# Silent_Stepper_Driver_X_Axis.net
KiCad netlist of a schematic drawn in EAGLE
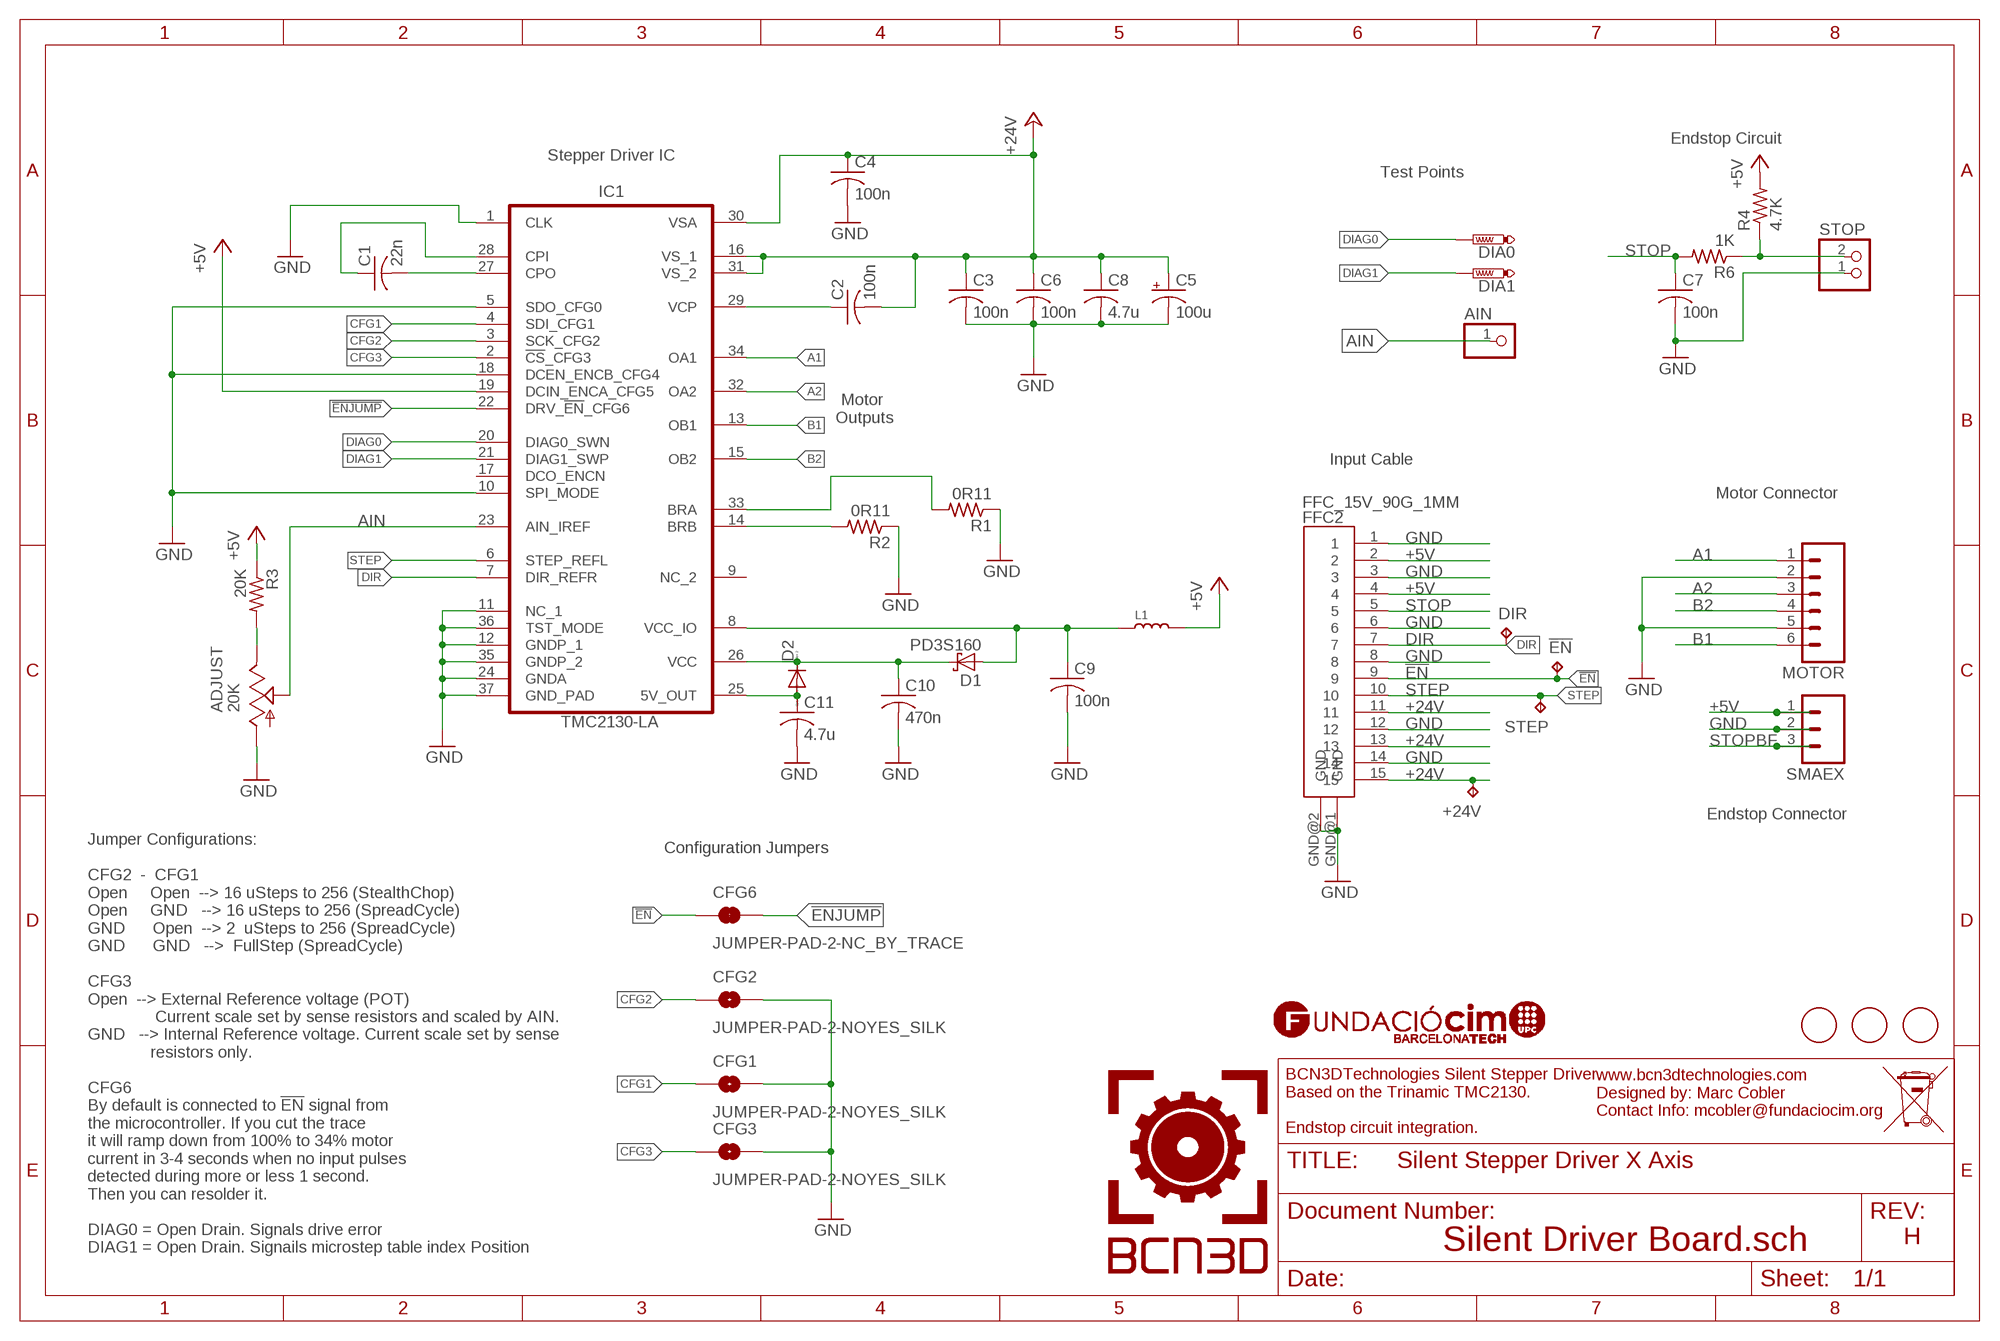
[diagram p0: schematic, sheet 1]

(export (version "E")
  (design (tool "Eeschema 10.0.6"))
  (components
    (comp (ref "!EN")
      (value "TPB1,27")
      (footprint "eagle-import:B1,27")
      (libsource (lib "eagle-import") (part "TPB1,27"))
    )
    (comp (ref "+24V")
      (value "TPB1,27")
      (footprint "eagle-import:B1,27")
      (libsource (lib "eagle-import") (part "TPB1,27"))
    )
    (comp (ref "ADJUST")
      (value "20K")
      (footprint "eagle-import:3223G")
      (fields (field (name "MF") "BOURNS") (field (name "MPN") "3314G-2-203E"))
      (libsource (lib "eagle-import") (part "TRIM_US-3223G"))
    )
    (comp (ref "AIN")
      (value "PINHD-1X1")
      (footprint "eagle-import:1X01")
      (libsource (lib "eagle-import") (part "PINHD-1X1"))
    )
    (comp (ref "C1")
      (value "22n")
      (footprint "eagle-import:C0603K")
      (fields (field (name "MF") "MURATA") (field (name "MPN") "GCM188R72A223KA37D"))
      (libsource (lib "eagle-import") (part "C-USC0603K"))
    )
    (comp (ref "C2")
      (value "100n")
      (footprint "eagle-import:C0603K")
      (fields (field (name "MF") "AVX") (field (name "MPN") "06035C104KAT2A"))
      (libsource (lib "eagle-import") (part "C-USC0603K"))
    )
    (comp (ref "C3")
      (value "100n")
      (footprint "eagle-import:C0603K")
      (fields (field (name "MF") "AVX") (field (name "MPN") "06035C104KAT2A"))
      (libsource (lib "eagle-import") (part "C-USC0603K"))
    )
    (comp (ref "C4")
      (value "100n")
      (footprint "eagle-import:C0603K")
      (fields (field (name "MF") "AVX") (field (name "MPN") "06035C104KAT2A"))
      (libsource (lib "eagle-import") (part "C-USC0603K"))
    )
    (comp (ref "C5")
      (value "100u")
      (footprint "eagle-import:UD-6,3X7,7_NICHICON")
      (fields (field (name "MF") "PANASONIC ELECTRONIC COMPONENTS") (field (name "MPN") "EEE1HA101UAP"))
      (libsource (lib "eagle-import") (part "CPOL-USUD-6,3X7,7"))
    )
    (comp (ref "C6")
      (value "100n")
      (footprint "eagle-import:C0603K")
      (fields (field (name "MF") "AVX") (field (name "MPN") "06035C104KAT2A"))
      (libsource (lib "eagle-import") (part "C-USC0603K"))
    )
    (comp (ref "C7")
      (value "100n")
      (footprint "eagle-import:C0603K")
      (fields (field (name "MF") "AVX") (field (name "MPN") "06035C104KAT2A"))
      (libsource (lib "eagle-import") (part "C-USC0603K"))
    )
    (comp (ref "C8")
      (value "4.7u")
      (footprint "eagle-import:C1210")
      (fields (field (name "MF") "KEMET") (field (name "MPN") "C1210X475K5RACTU"))
      (libsource (lib "eagle-import") (part "C-USC1210"))
    )
    (comp (ref "C9")
      (value "100n")
      (footprint "eagle-import:C0603K")
      (fields (field (name "MF") "AVX") (field (name "MPN") "06035C104KAT2A"))
      (libsource (lib "eagle-import") (part "C-USC0603K"))
    )
    (comp (ref "C10")
      (value "470n")
      (footprint "eagle-import:C0603K")
      (fields (field (name "MF") "MURATA") (field (name "MPN") "GRM188R71C474KA88D"))
      (libsource (lib "eagle-import") (part "C-USC0603K"))
    )
    (comp (ref "C11")
      (value "4.7u")
      (footprint "eagle-import:C0805")
      (fields (field (name "MF") "AVX") (field (name "MPN") "0805YC475KAT2A"))
      (libsource (lib "eagle-import") (part "C-USC0805"))
    )
    (comp (ref "CFG1")
      (value "JUMPER-PAD-2-NOYES_SILK")
      (footprint "eagle-import:PAD-JUMPER-2-NO_YES_SILK")
      (libsource (lib "eagle-import") (part "JUMPER-PAD-2-NOYES_SILK"))
    )
    (comp (ref "CFG2")
      (value "JUMPER-PAD-2-NOYES_SILK")
      (footprint "eagle-import:PAD-JUMPER-2-NO_YES_SILK")
      (libsource (lib "eagle-import") (part "JUMPER-PAD-2-NOYES_SILK"))
    )
    (comp (ref "CFG3")
      (value "JUMPER-PAD-2-NOYES_SILK")
      (footprint "eagle-import:PAD-JUMPER-2-NO_YES_SILK")
      (libsource (lib "eagle-import") (part "JUMPER-PAD-2-NOYES_SILK"))
    )
    (comp (ref "CFG6")
      (value "JUMPER-PAD-2-NC_BY_TRACE")
      (footprint "eagle-import:PAD-JUMPER-2-NC_BY_TRACE_YES_SILK")
      (libsource (lib "eagle-import") (part "JUMPER-PAD-2-NC_BY_TRACE"))
    )
    (comp (ref "D1")
      (value "PD3S160")
      (footprint "eagle-import:POWERDI323")
      (fields (field (name "MF") "DIODES INC.") (field (name "MPN") "PD3S160-7"))
      (libsource (lib "eagle-import") (part "PD3S160"))
    )
    (comp (ref "D2")
      (value "DIODE-MINIMELF")
      (footprint "eagle-import:MINIMELF")
      (fields (field (name "MF") "NXP") (field (name "MPN") "PMLL4448"))
      (libsource (lib "eagle-import") (part "DIODE-MINIMELF"))
    )
    (comp (ref "DIA0")
      (value "PTR1TP12R")
      (footprint "eagle-import:TP12R")
      (libsource (lib "eagle-import") (part "PTR1TP12R"))
    )
    (comp (ref "DIA1")
      (value "PTR1TP12R")
      (footprint "eagle-import:TP12R")
      (libsource (lib "eagle-import") (part "PTR1TP12R"))
    )
    (comp (ref "DIR")
      (value "TPB1,27")
      (footprint "eagle-import:B1,27")
      (libsource (lib "eagle-import") (part "TPB1,27"))
    )
    (comp (ref "FFC2")
      (value "FFC_15V_90G_1MM")
      (footprint "eagle-import:TE_FFC_CON1MM")
      (libsource (lib "eagle-import") (part "FFC_15V_90G_1MM"))
    )
    (comp (ref "IC1")
      (value "TMC2130-LA")
      (footprint "eagle-import:TMC_QFN36_0.5_5.0X6.0")
      (fields (field (name "MANUFACTURER") " TRINAMIC "))
      (libsource (lib "eagle-import") (part "TMC2130-LA"))
    )
    (comp (ref "L1")
      (value "INDUCTOR/FERRITE-BEAD'0603'")
      (footprint "eagle-import:L0603")
      (fields (field (name "MF") "BOURNS") (field (name "MPN") "CRL0603-FW-R470ELF"))
      (libsource (lib "eagle-import") (part "INDUCTOR/FERRITE-BEAD'0603'"))
    )
    (comp (ref "MOTOR")
      (value "M06")
      (footprint "eagle-import:JST-6-PTH")
      (fields
        (field (name "MF") "JST (JAPAN SOLDERLESS TERMINALS)")
        (field (name "MPN") "S6B-PH-K-S (LF)(SN)")
      )
      (libsource (lib "eagle-import") (part "M06"))
    )
    (comp (ref "R1")
      (value "0R11")
      (footprint "eagle-import:R0805")
      (fields (field (name "MF") "PANASONIC ELECTRONIC COMPONENTS") (field (name "MPN") "ERJ6BSFR11V"))
      (libsource (lib "eagle-import") (part "R-US_R0805"))
    )
    (comp (ref "R2")
      (value "0R11")
      (footprint "eagle-import:R0805")
      (fields (field (name "MF") "PANASONIC ELECTRONIC COMPONENTS") (field (name "MPN") "ERJ6BSFR11V"))
      (libsource (lib "eagle-import") (part "R-US_R0805"))
    )
    (comp (ref "R3")
      (value "20K")
      (footprint "eagle-import:R0603")
      (fields (field (name "MF") "MULTICOMP") (field (name "MPN") "MC0201L6F2002SE."))
      (libsource (lib "eagle-import") (part "R-US_R0603"))
    )
    (comp (ref "R4")
      (value "4.7K")
      (footprint "eagle-import:R0603")
      (fields (field (name "MF") "PANASONIC ELECTRONIC COMPONENTS") (field (name "MPN") "ERJP06F4701V"))
      (libsource (lib "eagle-import") (part "R-US_R0603"))
    )
    (comp (ref "R6")
      (value "1K")
      (footprint "eagle-import:R0603")
      (fields (field (name "MF") "BOURNS") (field (name "MPN") "CR0805-JW-102ELF"))
      (libsource (lib "eagle-import") (part "R-US_R0603"))
    )
    (comp (ref "SMAEX")
      (value "M03PTH")
      (footprint "eagle-import:1X03")
      (libsource (lib "eagle-import") (part "M03PTH"))
    )
    (comp (ref "STEP")
      (value "TPB1,27")
      (footprint "eagle-import:B1,27")
      (libsource (lib "eagle-import") (part "TPB1,27"))
    )
    (comp (ref "STOP")
      (value "JST_2PIN-THM-RA")
      (footprint "eagle-import:JST-PH-2-THM-RA")
      (fields
        (field (name "MF") "JST (JAPAN SOLDERLESS TERMINALS)")
        (field (name "MPN") "S2B-PH-K-S (LF)(SN)")
      )
      (libsource (lib "eagle-import") (part "JST_2PIN-THM-RA"))
    )
    (comp (ref "U$2")
      (value "FIDUCIAL")
      (footprint "eagle-import:FIDUCIAL_1MM")
      (libsource (lib "eagle-import") (part "FIDUCIAL"))
    )
    (comp (ref "U$3")
      (value "FIDUCIAL")
      (footprint "eagle-import:FIDUCIAL_1MM")
      (libsource (lib "eagle-import") (part "FIDUCIAL"))
    )
    (comp (ref "U$4")
      (value "FIDUCIAL")
      (footprint "eagle-import:FIDUCIAL_1MM")
      (libsource (lib "eagle-import") (part "FIDUCIAL"))
    )
  )
  (nets
    (net (code "1") (name "+5V") (class "Default")
      (node (ref "FFC2") (pin "2") (pinfunction "2_2") (pintype "bidirectional"))
      (node (ref "FFC2") (pin "4") (pinfunction "4_4") (pintype "bidirectional"))
      (node (ref "IC1") (pin "19") (pinfunction "DCIN_ENCA_CFG5_19") (pintype "input"))
      (node (ref "L1") (pin "2") (pinfunction "2_2") (pintype "passive"))
      (node (ref "R3") (pin "1") (pinfunction "1_1") (pintype "passive"))
      (node (ref "R4") (pin "2") (pinfunction "2_2") (pintype "passive"))
      (node (ref "SMAEX") (pin "1") (pinfunction "1_1") (pintype "passive"))
    )
    (net (code "2") (name "+24V") (class "Default")
      (node (ref "+24V") (pin "TP") (pinfunction "TP_TP") (pintype "input"))
      (node (ref "C2") (pin "2") (pinfunction "2_2") (pintype "passive"))
      (node (ref "C3") (pin "1") (pinfunction "1_1") (pintype "passive"))
      (node (ref "C4") (pin "1") (pinfunction "1_1") (pintype "passive"))
      (node (ref "C5") (pin "+") (pinfunction "+_+") (pintype "passive"))
      (node (ref "C6") (pin "1") (pinfunction "1_1") (pintype "passive"))
      (node (ref "C8") (pin "1") (pinfunction "1_1") (pintype "passive"))
      (node (ref "FFC2") (pin "11") (pinfunction "11_11") (pintype "bidirectional"))
      (node (ref "FFC2") (pin "13") (pinfunction "13_13") (pintype "bidirectional"))
      (node (ref "FFC2") (pin "15") (pinfunction "15_15") (pintype "bidirectional"))
      (node (ref "IC1") (pin "16") (pinfunction "VS_1_16") (pintype "power_in"))
      (node (ref "IC1") (pin "30") (pinfunction "VSA_30") (pintype "power_in"))
      (node (ref "IC1") (pin "31") (pinfunction "VS_2_31") (pintype "power_in"))
    )
    (net (code "3") (name "/STOP") (class "Default")
      (node (ref "C7") (pin "1") (pinfunction "1_1") (pintype "passive"))
      (node (ref "FFC2") (pin "5") (pinfunction "5_5") (pintype "bidirectional"))
      (node (ref "R6") (pin "2") (pinfunction "2_2") (pintype "passive"))
    )
    (net (code "4") (name "/STOPBF") (class "Default")
      (node (ref "R4") (pin "1") (pinfunction "1_1") (pintype "passive"))
      (node (ref "R6") (pin "1") (pinfunction "1_1") (pintype "passive"))
      (node (ref "SMAEX") (pin "3") (pinfunction "3_3") (pintype "passive"))
      (node (ref "STOP") (pin "2") (pinfunction "1_2") (pintype "passive"))
    )
    (net (code "5") (name "/~{ENJUMP}") (class "Default")
      (node (ref "CFG6") (pin "2") (pinfunction "2_2") (pintype "passive"))
      (node (ref "IC1") (pin "22") (pinfunction "DRV_~{EN}_CFG6_22") (pintype "input"))
    )
    (net (code "6") (name "/~{EN}") (class "Default")
      (node (ref "!EN") (pin "TP") (pinfunction "TP_TP") (pintype "input"))
      (node (ref "CFG6") (pin "1") (pinfunction "1_1") (pintype "passive"))
      (node (ref "FFC2") (pin "9") (pinfunction "9_9") (pintype "bidirectional"))
    )
    (net (code "7") (name "A1") (class "Default")
      (node (ref "IC1") (pin "34") (pinfunction "OA1_34") (pintype "output"))
      (node (ref "MOTOR") (pin "1") (pinfunction "1_1") (pintype "passive"))
    )
    (net (code "8") (name "A2") (class "Default")
      (node (ref "IC1") (pin "32") (pinfunction "OA2_32") (pintype "output"))
      (node (ref "MOTOR") (pin "3") (pinfunction "3_3") (pintype "passive"))
    )
    (net (code "9") (name "AIN") (class "Default")
      (node (ref "ADJUST") (pin "2") (pinfunction "S_2") (pintype "passive"))
      (node (ref "AIN") (pin "1") (pinfunction "1_1") (pintype "passive"))
      (node (ref "IC1") (pin "23") (pinfunction "AIN_IREF_23") (pintype "input"))
    )
    (net (code "10") (name "B1") (class "Default")
      (node (ref "IC1") (pin "13") (pinfunction "OB1_13") (pintype "output"))
      (node (ref "MOTOR") (pin "6") (pinfunction "6_6") (pintype "passive"))
    )
    (net (code "11") (name "B2") (class "Default")
      (node (ref "IC1") (pin "15") (pinfunction "OB2_15") (pintype "output"))
      (node (ref "MOTOR") (pin "4") (pinfunction "4_4") (pintype "passive"))
    )
    (net (code "12") (name "CFG1") (class "Default")
      (node (ref "CFG1") (pin "1") (pinfunction "1_1") (pintype "passive"))
      (node (ref "IC1") (pin "4") (pinfunction "SDI_CFG1_4") (pintype "input"))
    )
    (net (code "13") (name "CFG2") (class "Default")
      (node (ref "CFG2") (pin "1") (pinfunction "1_1") (pintype "passive"))
      (node (ref "IC1") (pin "3") (pinfunction "SCK_CFG2_3") (pintype "input"))
    )
    (net (code "14") (name "CFG3") (class "Default")
      (node (ref "CFG3") (pin "1") (pinfunction "1_1") (pintype "passive"))
      (node (ref "IC1") (pin "2") (pinfunction "~{CS}_CFG3_2") (pintype "input"))
    )
    (net (code "15") (name "DIAG0") (class "Default")
      (node (ref "DIA0") (pin "TP") (pinfunction "TP_TP") (pintype "input"))
      (node (ref "IC1") (pin "20") (pinfunction "DIAG0_SWN_20") (pintype "bidirectional"))
    )
    (net (code "16") (name "DIAG1") (class "Default")
      (node (ref "DIA1") (pin "TP") (pinfunction "TP_TP") (pintype "input"))
      (node (ref "IC1") (pin "21") (pinfunction "DIAG1_SWP_21") (pintype "bidirectional"))
    )
    (net (code "17") (name "DIR") (class "Default")
      (node (ref "DIR") (pin "TP") (pinfunction "TP_TP") (pintype "input"))
      (node (ref "FFC2") (pin "7") (pinfunction "7_7") (pintype "bidirectional"))
      (node (ref "IC1") (pin "7") (pinfunction "DIR_REFR_7") (pintype "input"))
    )
    (net (code "18") (name "GND") (class "Default")
      (node (ref "ADJUST") (pin "1") (pinfunction "A_1") (pintype "passive"))
      (node (ref "C10") (pin "2") (pinfunction "2_2") (pintype "passive"))
      (node (ref "C11") (pin "2") (pinfunction "2_2") (pintype "passive"))
      (node (ref "C3") (pin "2") (pinfunction "2_2") (pintype "passive"))
      (node (ref "C4") (pin "2") (pinfunction "2_2") (pintype "passive"))
      (node (ref "C5") (pin "-") (pinfunction "-_-") (pintype "passive"))
      (node (ref "C6") (pin "2") (pinfunction "2_2") (pintype "passive"))
      (node (ref "C7") (pin "2") (pinfunction "2_2") (pintype "passive"))
      (node (ref "C8") (pin "2") (pinfunction "2_2") (pintype "passive"))
      (node (ref "C9") (pin "2") (pinfunction "2_2") (pintype "passive"))
      (node (ref "CFG1") (pin "2") (pinfunction "2_2") (pintype "passive"))
      (node (ref "CFG2") (pin "2") (pinfunction "2_2") (pintype "passive"))
      (node (ref "CFG3") (pin "2") (pinfunction "2_2") (pintype "passive"))
      (node (ref "FFC2") (pin "1") (pinfunction "1_1") (pintype "bidirectional"))
      (node (ref "FFC2") (pin "12") (pinfunction "12_12") (pintype "bidirectional"))
      (node (ref "FFC2") (pin "14") (pinfunction "14_14") (pintype "bidirectional"))
      (node (ref "FFC2") (pin "3") (pinfunction "3_3") (pintype "bidirectional"))
      (node (ref "FFC2") (pin "6") (pinfunction "6_6") (pintype "bidirectional"))
      (node (ref "FFC2") (pin "8") (pinfunction "8_8") (pintype "bidirectional"))
      (node (ref "FFC2") (pin "GND@1") (pinfunction "GND_GND@1") (pintype "bidirectional"))
      (node (ref "FFC2") (pin "GND@2") (pinfunction "GND_GND@2") (pintype "bidirectional"))
      (node (ref "IC1") (pin "1") (pinfunction "CLK_1") (pintype "input"))
      (node (ref "IC1") (pin "10") (pinfunction "SPI_MODE_10") (pintype "input"))
      (node (ref "IC1") (pin "11") (pinfunction "NC_1_11") (pintype "power_in"))
      (node (ref "IC1") (pin "12") (pinfunction "GNDP_1_12") (pintype "power_in"))
      (node (ref "IC1") (pin "18") (pinfunction "DCEN_ENCB_CFG4_18") (pintype "input"))
      (node (ref "IC1") (pin "24") (pinfunction "GNDA_24") (pintype "power_in"))
      (node (ref "IC1") (pin "35") (pinfunction "GNDP_2_35") (pintype "power_in"))
      (node (ref "IC1") (pin "36") (pinfunction "TST_MODE_36") (pintype "input"))
      (node (ref "IC1") (pin "37") (pinfunction "GND_PAD_37") (pintype "power_in"))
      (node (ref "IC1") (pin "5") (pinfunction "SDO_CFG0_5") (pintype "bidirectional"))
      (node (ref "MOTOR") (pin "2") (pinfunction "2_2") (pintype "passive"))
      (node (ref "MOTOR") (pin "5") (pinfunction "5_5") (pintype "passive"))
      (node (ref "R1") (pin "1") (pinfunction "1_1") (pintype "passive"))
      (node (ref "R2") (pin "1") (pinfunction "1_1") (pintype "passive"))
      (node (ref "SMAEX") (pin "2") (pinfunction "2_2") (pintype "passive"))
      (node (ref "STOP") (pin "1") (pinfunction "2_1") (pintype "passive"))
    )
    (net (code "19") (name "Net-(ADJUST-E)") (class "Default")
      (node (ref "ADJUST") (pin "3") (pinfunction "E_3") (pintype "passive"))
      (node (ref "R3") (pin "2") (pinfunction "2_2") (pintype "passive"))
    )
    (net (code "20") (name "Net-(IC1-5V_OUT)") (class "Default")
      (node (ref "C11") (pin "1") (pinfunction "1_1") (pintype "passive"))
      (node (ref "D2") (pin "A") (pinfunction "A_A") (pintype "passive"))
      (node (ref "IC1") (pin "25") (pinfunction "5V_OUT_25") (pintype "power_in"))
    )
    (net (code "21") (name "Net-(IC1-BRA)") (class "Default")
      (node (ref "IC1") (pin "33") (pinfunction "BRA_33") (pintype "output"))
      (node (ref "R1") (pin "2") (pinfunction "2_2") (pintype "passive"))
    )
    (net (code "22") (name "Net-(IC1-BRB)") (class "Default")
      (node (ref "IC1") (pin "14") (pinfunction "BRB_14") (pintype "output"))
      (node (ref "R2") (pin "2") (pinfunction "2_2") (pintype "passive"))
    )
    (net (code "23") (name "Net-(IC1-CPI)") (class "Default")
      (node (ref "C1") (pin "1") (pinfunction "1_1") (pintype "passive"))
      (node (ref "IC1") (pin "28") (pinfunction "CPI_28") (pintype "input"))
    )
    (net (code "24") (name "Net-(IC1-CPO)") (class "Default")
      (node (ref "C1") (pin "2") (pinfunction "2_2") (pintype "passive"))
      (node (ref "IC1") (pin "27") (pinfunction "CPO_27") (pintype "output"))
    )
    (net (code "25") (name "Net-(IC1-VCC)") (class "Default")
      (node (ref "C10") (pin "1") (pinfunction "1_1") (pintype "passive"))
      (node (ref "D1") (pin "C") (pinfunction "C_C") (pintype "passive"))
      (node (ref "D2") (pin "C") (pinfunction "C_C") (pintype "passive"))
      (node (ref "IC1") (pin "26") (pinfunction "VCC_26") (pintype "power_in"))
    )
    (net (code "26") (name "Net-(IC1-VCC_IO)") (class "Default")
      (node (ref "C9") (pin "1") (pinfunction "1_1") (pintype "passive"))
      (node (ref "D1") (pin "A") (pinfunction "A_A") (pintype "passive"))
      (node (ref "IC1") (pin "8") (pinfunction "VCC_IO_8") (pintype "power_in"))
      (node (ref "L1") (pin "1") (pinfunction "1_1") (pintype "passive"))
    )
    (net (code "27") (name "Net-(IC1-VCP)") (class "Default")
      (node (ref "C2") (pin "1") (pinfunction "1_1") (pintype "passive"))
      (node (ref "IC1") (pin "29") (pinfunction "VCP_29") (pintype "power_in"))
    )
    (net (code "28") (name "STEP") (class "Default")
      (node (ref "FFC2") (pin "10") (pinfunction "10_10") (pintype "bidirectional"))
      (node (ref "IC1") (pin "6") (pinfunction "STEP_REFL_6") (pintype "input"))
      (node (ref "STEP") (pin "TP") (pinfunction "TP_TP") (pintype "input"))
    )
    (net (code "29") (name "unconnected-(IC1-DCO_ENCN-Pad17)") (class "Default")
      (node (ref "IC1") (pin "17") (pinfunction "DCO_ENCN_17") (pintype "bidirectional"))
    )
    (net (code "30") (name "unconnected-(IC1-NC_2-Pad9)") (class "Default")
      (node (ref "IC1") (pin "9") (pinfunction "NC_2_9") (pintype "passive"))
    )
  )
)
